# redmaus-ir-tx-amp-mk-1_0.net
KiCad netlist of a schematic drawn in EAGLE
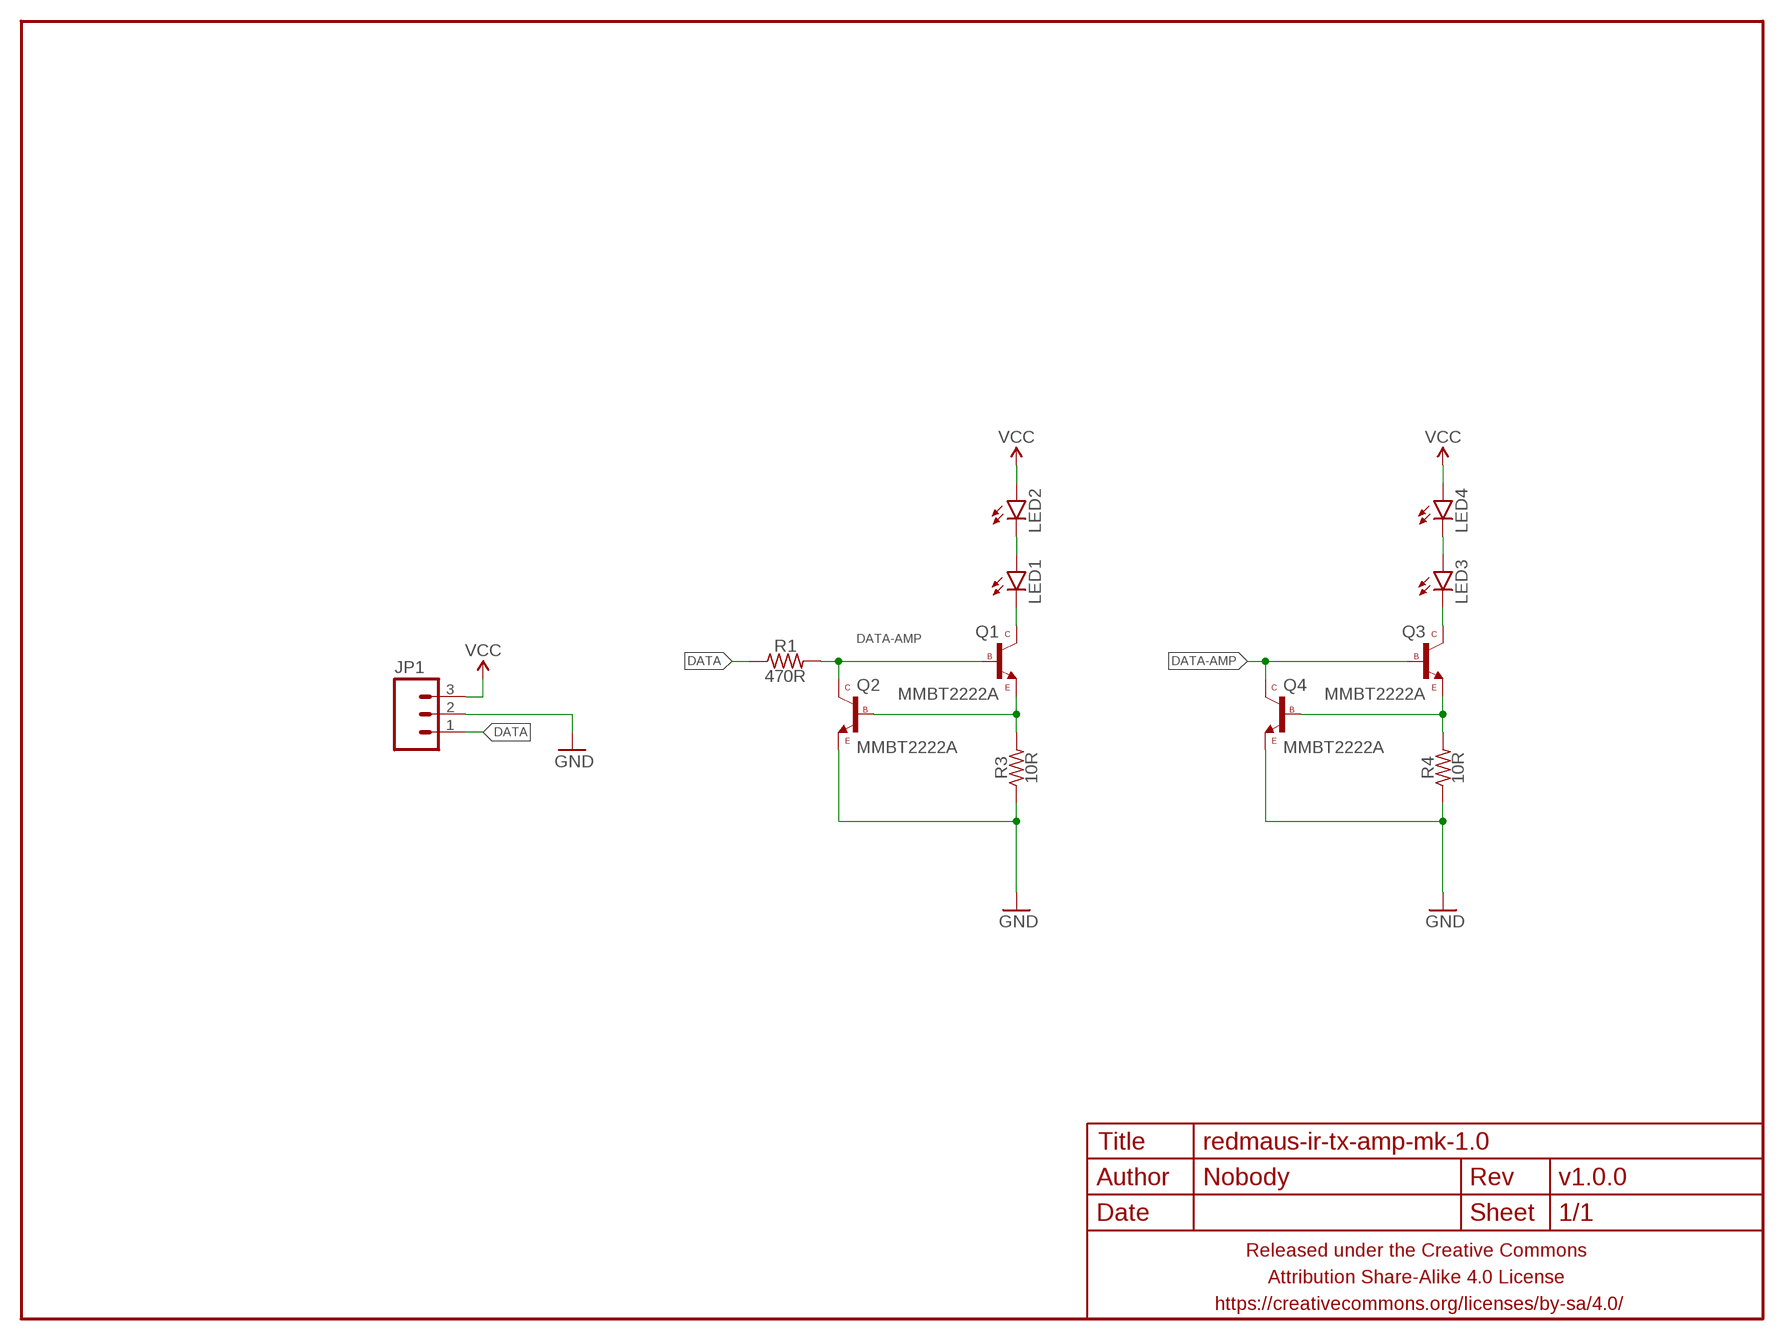
[diagram p0: schematic, sheet 1]

(export (version "E")
  (design (tool "Eeschema 10.0.6"))
  (components
    (comp (ref "FRAME1")
      (value "FRAME-LETTERNO_PACKAGE")
      (footprint "eagle-import:DUMMY")
      (fields (field (name "VERSION") "v1.0.0") (field (name "DESIGNER") "Nobody"))
      (libsource (lib "eagle-import") (part "FRAME-LETTERNO_PACKAGE"))
    )
    (comp (ref "JP1")
      (value "M03PTH-CENTERED")
      (footprint "eagle-import:1X03-CENTERED")
      (libsource (lib "eagle-import") (part "M03PTH-CENTERED"))
    )
    (comp (ref "LED1")
      (value "LED5MM_SHORTPADS")
      (footprint "eagle-import:LED5MM_SHORTPADS")
      (libsource (lib "eagle-import") (part "LED5MM_SHORTPADS"))
    )
    (comp (ref "LED2")
      (value "LED5MM_SHORTPADS")
      (footprint "eagle-import:LED5MM_SHORTPADS")
      (libsource (lib "eagle-import") (part "LED5MM_SHORTPADS"))
    )
    (comp (ref "LED3")
      (value "LED5MM_SHORTPADS")
      (footprint "eagle-import:LED5MM_SHORTPADS")
      (libsource (lib "eagle-import") (part "LED5MM_SHORTPADS"))
    )
    (comp (ref "LED4")
      (value "LED5MM_SHORTPADS")
      (footprint "eagle-import:LED5MM_SHORTPADS")
      (libsource (lib "eagle-import") (part "LED5MM_SHORTPADS"))
    )
    (comp (ref "Q1")
      (value "MMBT2222A")
      (footprint "eagle-import:SOT23")
      (libsource (lib "eagle-import") (part "TRANSISTOR_NPNMMBT2222A"))
    )
    (comp (ref "Q2")
      (value "MMBT2222A")
      (footprint "eagle-import:SOT23")
      (libsource (lib "eagle-import") (part "TRANSISTOR_NPNMMBT2222A"))
    )
    (comp (ref "Q3")
      (value "MMBT2222A")
      (footprint "eagle-import:SOT23")
      (libsource (lib "eagle-import") (part "TRANSISTOR_NPNMMBT2222A"))
    )
    (comp (ref "Q4")
      (value "MMBT2222A")
      (footprint "eagle-import:SOT23")
      (libsource (lib "eagle-import") (part "TRANSISTOR_NPNMMBT2222A"))
    )
    (comp (ref "R1")
      (value "470R")
      (footprint "eagle-import:R0603-TIGHTER")
      (libsource (lib "eagle-import") (part "RESISTORR0603-TIGHTER"))
    )
    (comp (ref "R3")
      (value "10R")
      (footprint "eagle-import:R0603-TIGHTER")
      (libsource (lib "eagle-import") (part "RESISTORR0603-TIGHTER"))
    )
    (comp (ref "R4")
      (value "10R")
      (footprint "eagle-import:R0603-TIGHTER")
      (libsource (lib "eagle-import") (part "RESISTORR0603-TIGHTER"))
    )
  )
  (nets
    (net (code "1") (name "DATA") (class "Default")
      (node (ref "JP1") (pin "1") (pinfunction "1_1") (pintype "passive"))
      (node (ref "R1") (pin "1") (pinfunction "1_1") (pintype "passive"))
    )
    (net (code "2") (name "DATA-AMP") (class "Default")
      (node (ref "Q1") (pin "1") (pinfunction "B_1") (pintype "passive"))
      (node (ref "Q2") (pin "3") (pinfunction "C_3") (pintype "passive"))
      (node (ref "Q3") (pin "1") (pinfunction "B_1") (pintype "passive"))
      (node (ref "Q4") (pin "3") (pinfunction "C_3") (pintype "passive"))
      (node (ref "R1") (pin "2") (pinfunction "2_2") (pintype "passive"))
    )
    (net (code "3") (name "GND") (class "Default")
      (node (ref "JP1") (pin "2") (pinfunction "2_2") (pintype "passive"))
      (node (ref "Q2") (pin "2") (pinfunction "E_2") (pintype "passive"))
      (node (ref "Q4") (pin "2") (pinfunction "E_2") (pintype "passive"))
      (node (ref "R3") (pin "1") (pinfunction "1_1") (pintype "passive"))
      (node (ref "R4") (pin "1") (pinfunction "1_1") (pintype "passive"))
    )
    (net (code "4") (name "Net-(LED1-C)") (class "Default")
      (node (ref "LED1") (pin "K") (pinfunction "C_K") (pintype "passive"))
      (node (ref "Q1") (pin "3") (pinfunction "C_3") (pintype "passive"))
    )
    (net (code "5") (name "Net-(LED2-C)") (class "Default")
      (node (ref "LED1") (pin "A") (pinfunction "A_A") (pintype "passive"))
      (node (ref "LED2") (pin "K") (pinfunction "C_K") (pintype "passive"))
    )
    (net (code "6") (name "Net-(LED3-C)") (class "Default")
      (node (ref "LED3") (pin "K") (pinfunction "C_K") (pintype "passive"))
      (node (ref "Q3") (pin "3") (pinfunction "C_3") (pintype "passive"))
    )
    (net (code "7") (name "Net-(LED4-C)") (class "Default")
      (node (ref "LED3") (pin "A") (pinfunction "A_A") (pintype "passive"))
      (node (ref "LED4") (pin "K") (pinfunction "C_K") (pintype "passive"))
    )
    (net (code "8") (name "Net-(Q1-E)") (class "Default")
      (node (ref "Q1") (pin "2") (pinfunction "E_2") (pintype "passive"))
      (node (ref "Q2") (pin "1") (pinfunction "B_1") (pintype "passive"))
      (node (ref "R3") (pin "2") (pinfunction "2_2") (pintype "passive"))
    )
    (net (code "9") (name "Net-(Q3-E)") (class "Default")
      (node (ref "Q3") (pin "2") (pinfunction "E_2") (pintype "passive"))
      (node (ref "Q4") (pin "1") (pinfunction "B_1") (pintype "passive"))
      (node (ref "R4") (pin "2") (pinfunction "2_2") (pintype "passive"))
    )
    (net (code "10") (name "VCC") (class "Default")
      (node (ref "JP1") (pin "3") (pinfunction "3_3") (pintype "passive"))
      (node (ref "LED2") (pin "A") (pinfunction "A_A") (pintype "passive"))
      (node (ref "LED4") (pin "A") (pinfunction "A_A") (pintype "passive"))
    )
  )
)
